# espslider.net
KiCad netlist of a schematic drawn in EAGLE
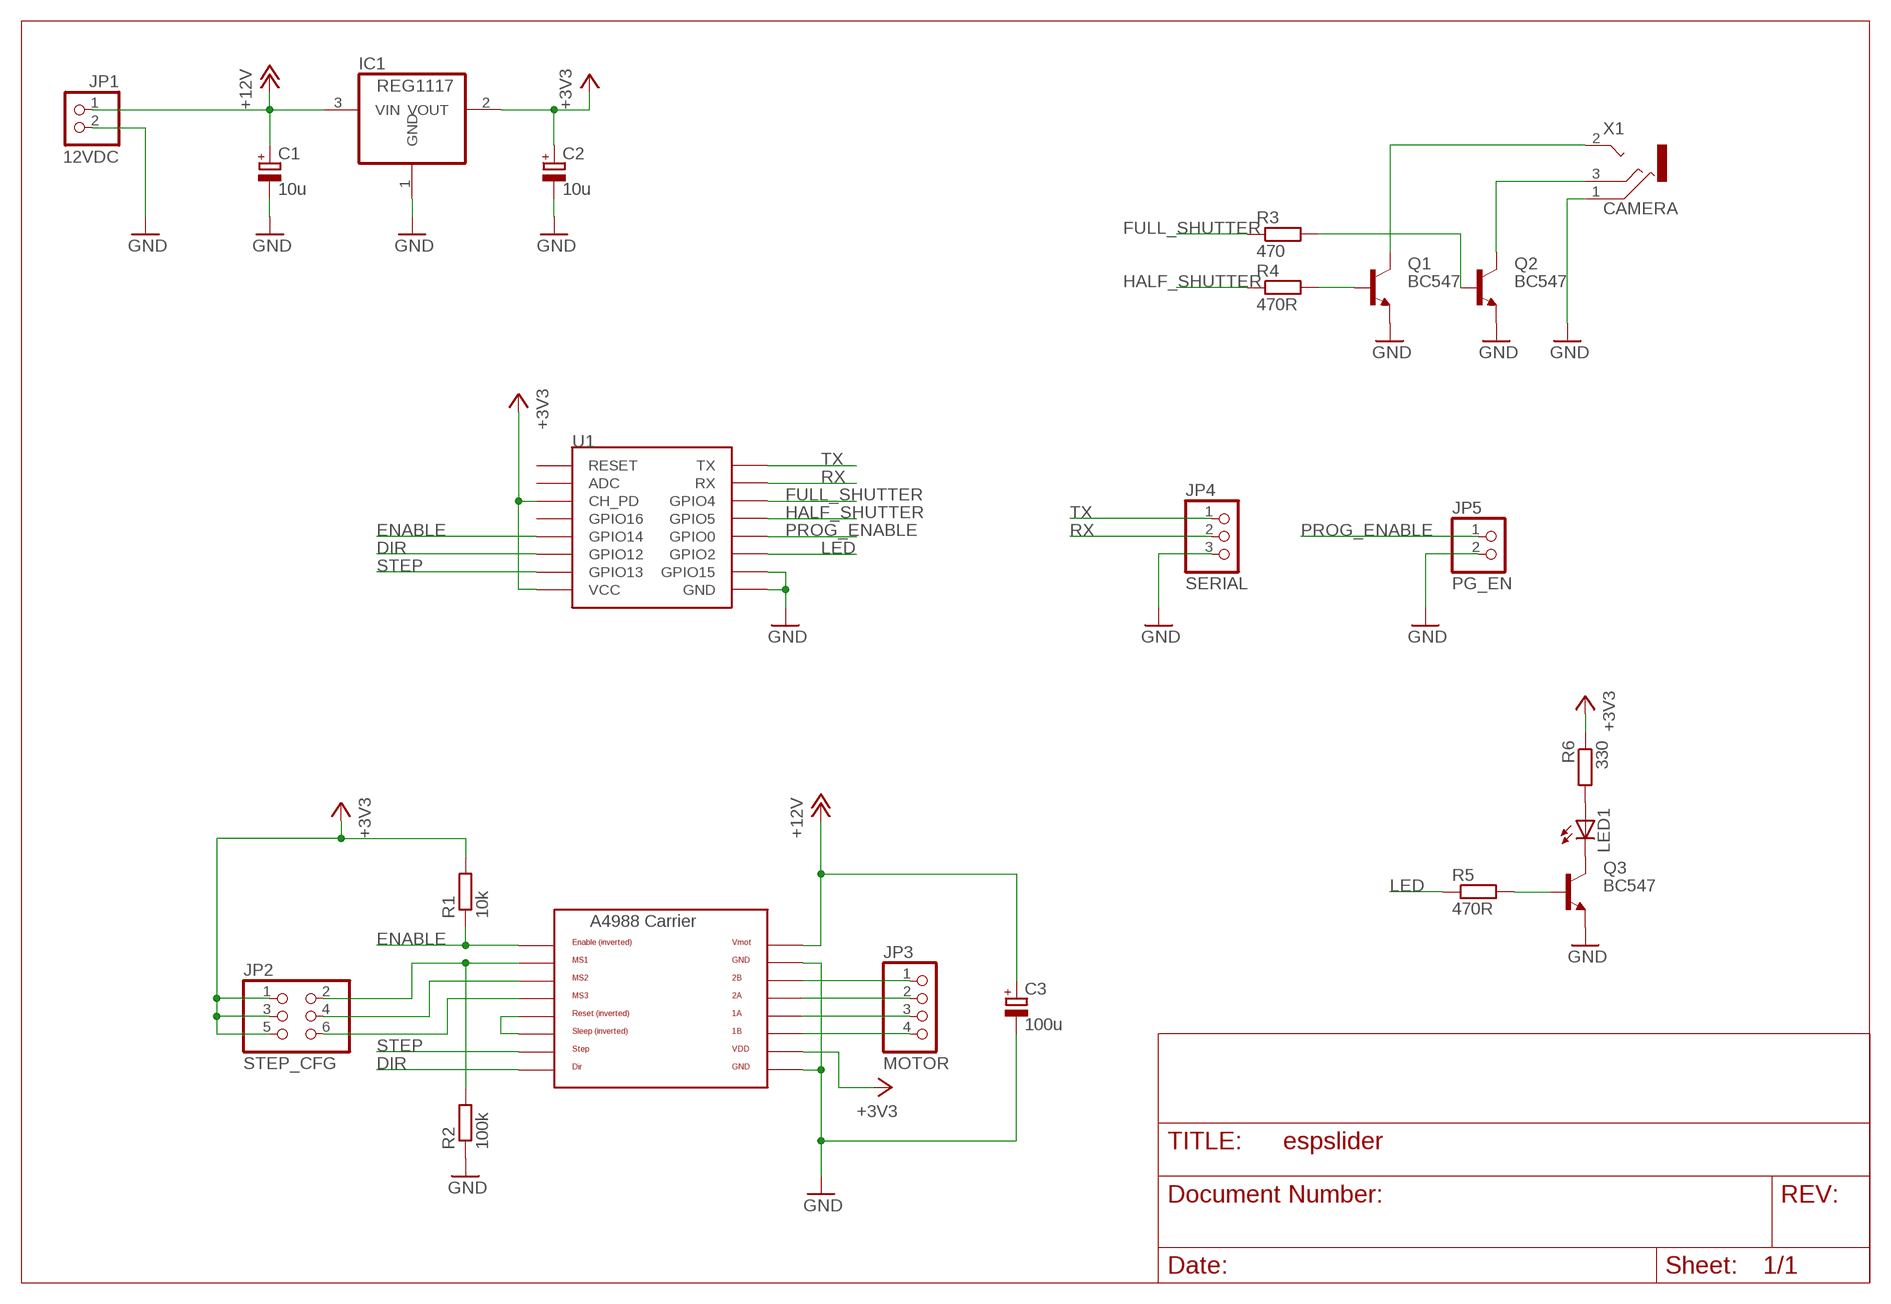
[diagram p0: schematic, sheet 1]

(export (version "E")
  (design (tool "Eeschema 10.0.6"))
  (components
    (comp (ref "C1")
      (value "10u")
      (footprint "eagle-import:E5-5")
      (fields (field (name "MF") "KEMET") (field (name "MPN") "T491C107K010AT"))
      (libsource (lib "eagle-import") (part "CPOL-EUE5-5"))
    )
    (comp (ref "C2")
      (value "10u")
      (footprint "eagle-import:E5-5")
      (fields (field (name "MF") "KEMET") (field (name "MPN") "T491C107K010AT"))
      (libsource (lib "eagle-import") (part "CPOL-EUE5-5"))
    )
    (comp (ref "C3")
      (value "100u")
      (footprint "eagle-import:E5-5")
      (libsource (lib "eagle-import") (part "CPOL-EUE5-5"))
    )
    (comp (ref "IC1")
      (value "REG1117")
      (footprint "eagle-import:SOT223")
      (libsource (lib "eagle-import") (part "REG1117"))
    )
    (comp (ref "JP1")
      (value "12VDC")
      (footprint "eagle-import:1X02")
      (libsource (lib "eagle-import") (part "PINHD-1X2"))
    )
    (comp (ref "JP2")
      (value "STEP_CFG")
      (footprint "eagle-import:2X03")
      (libsource (lib "eagle-import") (part "PINHD-2X3"))
    )
    (comp (ref "JP3")
      (value "MOTOR")
      (footprint "eagle-import:1X04")
      (libsource (lib "eagle-import") (part "PINHD-1X4"))
    )
    (comp (ref "JP4")
      (value "SERIAL")
      (footprint "eagle-import:1X03")
      (libsource (lib "eagle-import") (part "PINHD-1X3"))
    )
    (comp (ref "JP5")
      (value "PG_EN")
      (footprint "eagle-import:1X02")
      (libsource (lib "eagle-import") (part "PINHD-1X2"))
    )
    (comp (ref "LED1")
      (value "LED3MM")
      (footprint "eagle-import:LED3MM")
      (libsource (lib "eagle-import") (part "LED3MM"))
    )
    (comp (ref "Q1")
      (value "BC547")
      (footprint "eagle-import:TO92")
      (libsource (lib "eagle-import") (part "BC547"))
    )
    (comp (ref "Q2")
      (value "BC547")
      (footprint "eagle-import:TO92")
      (libsource (lib "eagle-import") (part "BC547"))
    )
    (comp (ref "Q3")
      (value "BC547")
      (footprint "eagle-import:TO92")
      (libsource (lib "eagle-import") (part "BC547"))
    )
    (comp (ref "R1")
      (value "10k")
      (footprint "eagle-import:0207_7")
      (libsource (lib "eagle-import") (part "R-EU_0207/7"))
    )
    (comp (ref "R2")
      (value "100k")
      (footprint "eagle-import:0207_15")
      (libsource (lib "eagle-import") (part "R-EU_0207/15"))
    )
    (comp (ref "R3")
      (value "470")
      (footprint "eagle-import:0207_7")
      (libsource (lib "eagle-import") (part "R-EU_0207/7"))
    )
    (comp (ref "R4")
      (value "470R")
      (footprint "eagle-import:0207_7")
      (libsource (lib "eagle-import") (part "R-EU_0207/7"))
    )
    (comp (ref "R5")
      (value "470R")
      (footprint "eagle-import:0207_7")
      (libsource (lib "eagle-import") (part "R-EU_0207/7"))
    )
    (comp (ref "R6")
      (value "330")
      (footprint "eagle-import:0207_7")
      (libsource (lib "eagle-import") (part "R-EU_0207/7"))
    )
    (comp (ref "U1")
      (value "ESP12SMD")
      (footprint "eagle-import:ESP12-SMD")
      (libsource (lib "eagle-import") (part "ESP12SMD"))
    )
    (comp (ref "U2")
      (value "A4988BREAKOUT")
      (footprint "eagle-import:A4988BREAKOUT")
      (libsource (lib "eagle-import") (part "A4988BREAKOUT"))
    )
    (comp (ref "X1")
      (value "CAMERA")
      (footprint "eagle-import:1501_05")
      (libsource (lib "eagle-import") (part "1501_04"))
    )
  )
  (nets
    (net (code "1") (name "+3V3") (class "Default")
      (node (ref "C2") (pin "+") (pinfunction "+_+") (pintype "passive"))
      (node (ref "IC1") (pin "2") (pinfunction "VOUT_2") (pintype "output"))
      (node (ref "JP2") (pin "1") (pinfunction "1_1") (pintype "passive"))
      (node (ref "JP2") (pin "3") (pinfunction "3_3") (pintype "passive"))
      (node (ref "JP2") (pin "5") (pinfunction "5_5") (pintype "passive"))
      (node (ref "R1") (pin "2") (pinfunction "2_2") (pintype "passive"))
      (node (ref "R6") (pin "1") (pinfunction "1_1") (pintype "passive"))
      (node (ref "U1") (pin "CH_PD") (pinfunction "CH_PD_CH_PD") (pintype "bidirectional"))
      (node (ref "U1") (pin "VCC") (pinfunction "VCC_VCC") (pintype "bidirectional"))
      (node (ref "U2") (pin "VDD") (pinfunction "VDD_VDD") (pintype "power_in"))
    )
    (net (code "2") (name "+12V") (class "Default")
      (node (ref "C1") (pin "+") (pinfunction "+_+") (pintype "passive"))
      (node (ref "C3") (pin "+") (pinfunction "+_+") (pintype "passive"))
      (node (ref "IC1") (pin "3") (pinfunction "VIN_3") (pintype "input"))
      (node (ref "JP1") (pin "1") (pinfunction "1_1") (pintype "passive"))
      (node (ref "U2") (pin "VMOT") (pinfunction "VMOT_VMOT") (pintype "power_in"))
    )
    (net (code "3") (name "/DIR") (class "Default")
      (node (ref "U1") (pin "GPIO12") (pinfunction "GPIO12_GPIO12") (pintype "bidirectional"))
      (node (ref "U2") (pin "DIR") (pinfunction "DIR_DIR") (pintype "input"))
    )
    (net (code "4") (name "/ENABLE") (class "Default")
      (node (ref "R1") (pin "1") (pinfunction "1_1") (pintype "passive"))
      (node (ref "U1") (pin "GPIO14") (pinfunction "GPIO14_GPIO14") (pintype "bidirectional"))
      (node (ref "U2") (pin "EN") (pinfunction "EN_EN") (pintype "input"))
    )
    (net (code "5") (name "/FULL_SHUTTER") (class "Default")
      (node (ref "R3") (pin "1") (pinfunction "1_1") (pintype "passive"))
      (node (ref "U1") (pin "GPIO4") (pinfunction "GPIO4_GPIO4") (pintype "bidirectional"))
    )
    (net (code "6") (name "/HALF_SHUTTER") (class "Default")
      (node (ref "R4") (pin "1") (pinfunction "1_1") (pintype "passive"))
      (node (ref "U1") (pin "GPIO5") (pinfunction "GPIO5_GPIO5") (pintype "bidirectional"))
    )
    (net (code "7") (name "/LED") (class "Default")
      (node (ref "R5") (pin "1") (pinfunction "1_1") (pintype "passive"))
      (node (ref "U1") (pin "GPIO2") (pinfunction "GPIO2_GPIO2") (pintype "bidirectional"))
    )
    (net (code "8") (name "/PROG_ENABLE") (class "Default")
      (node (ref "JP5") (pin "1") (pinfunction "1_1") (pintype "passive"))
      (node (ref "U1") (pin "GPIO0") (pinfunction "GPIO0_GPIO0") (pintype "bidirectional"))
    )
    (net (code "9") (name "/RX") (class "Default")
      (node (ref "JP4") (pin "2") (pinfunction "2_2") (pintype "passive"))
      (node (ref "U1") (pin "RXD0") (pinfunction "RX_RXD0") (pintype "bidirectional"))
    )
    (net (code "10") (name "/STEP") (class "Default")
      (node (ref "U1") (pin "GPIO13") (pinfunction "GPIO13_GPIO13") (pintype "bidirectional"))
      (node (ref "U2") (pin "STEP") (pinfunction "STEP_STEP") (pintype "input"))
    )
    (net (code "11") (name "/TX") (class "Default")
      (node (ref "JP4") (pin "1") (pinfunction "1_1") (pintype "passive"))
      (node (ref "U1") (pin "TXD0") (pinfunction "TX_TXD0") (pintype "bidirectional"))
    )
    (net (code "12") (name "GND") (class "Default")
      (node (ref "C1") (pin "-") (pinfunction "-_-") (pintype "passive"))
      (node (ref "C2") (pin "-") (pinfunction "-_-") (pintype "passive"))
      (node (ref "C3") (pin "-") (pinfunction "-_-") (pintype "passive"))
      (node (ref "IC1") (pin "1") (pinfunction "GND_1") (pintype "power_in"))
      (node (ref "JP1") (pin "2") (pinfunction "2_2") (pintype "passive"))
      (node (ref "JP4") (pin "3") (pinfunction "3_3") (pintype "passive"))
      (node (ref "JP5") (pin "2") (pinfunction "2_2") (pintype "passive"))
      (node (ref "Q1") (pin "1") (pinfunction "E_1") (pintype "passive"))
      (node (ref "Q2") (pin "1") (pinfunction "E_1") (pintype "passive"))
      (node (ref "Q3") (pin "1") (pinfunction "E_1") (pintype "passive"))
      (node (ref "R2") (pin "1") (pinfunction "1_1") (pintype "passive"))
      (node (ref "U1") (pin "GND") (pinfunction "GND_GND") (pintype "bidirectional"))
      (node (ref "U1") (pin "GPIO15") (pinfunction "GPIO15_GPIO15") (pintype "bidirectional"))
      (node (ref "U2") (pin "GND") (pinfunction "GND_GND") (pintype "power_in"))
      (node (ref "U2") (pin "GND@0") (pinfunction "GND_GND@0") (pintype "power_in"))
      (node (ref "X1") (pin "1") (pinfunction "1_1") (pintype "passive"))
    )
    (net (code "13") (name "Net-(JP2-Pad2)") (class "Default")
      (node (ref "JP2") (pin "2") (pinfunction "2_2") (pintype "passive"))
      (node (ref "R2") (pin "2") (pinfunction "2_2") (pintype "passive"))
      (node (ref "U2") (pin "MS1") (pinfunction "MS1_MS1") (pintype "input"))
    )
    (net (code "14") (name "Net-(JP2-Pad4)") (class "Default")
      (node (ref "JP2") (pin "4") (pinfunction "4_4") (pintype "passive"))
      (node (ref "U2") (pin "MS2") (pinfunction "MS2_MS2") (pintype "input"))
    )
    (net (code "15") (name "Net-(JP2-Pad6)") (class "Default")
      (node (ref "JP2") (pin "6") (pinfunction "6_6") (pintype "passive"))
      (node (ref "U2") (pin "MS3") (pinfunction "MS3_MS3") (pintype "input"))
    )
    (net (code "16") (name "Net-(JP3-Pad1)") (class "Default")
      (node (ref "JP3") (pin "1") (pinfunction "1_1") (pintype "passive"))
      (node (ref "U2") (pin "2B") (pinfunction "2B_2B") (pintype "output"))
    )
    (net (code "17") (name "Net-(JP3-Pad2)") (class "Default")
      (node (ref "JP3") (pin "2") (pinfunction "2_2") (pintype "passive"))
      (node (ref "U2") (pin "2A") (pinfunction "2A_2A") (pintype "output"))
    )
    (net (code "18") (name "Net-(JP3-Pad3)") (class "Default")
      (node (ref "JP3") (pin "3") (pinfunction "3_3") (pintype "passive"))
      (node (ref "U2") (pin "1A") (pinfunction "1A_1A") (pintype "output"))
    )
    (net (code "19") (name "Net-(JP3-Pad4)") (class "Default")
      (node (ref "JP3") (pin "4") (pinfunction "4_4") (pintype "passive"))
      (node (ref "U2") (pin "1B") (pinfunction "1B_1B") (pintype "output"))
    )
    (net (code "20") (name "Net-(LED1-C)") (class "Default")
      (node (ref "LED1") (pin "K") (pinfunction "C_K") (pintype "passive"))
      (node (ref "Q3") (pin "3") (pinfunction "C_3") (pintype "passive"))
    )
    (net (code "21") (name "Net-(LED1-PadA)") (class "Default")
      (node (ref "LED1") (pin "A") (pinfunction "A_A") (pintype "passive"))
      (node (ref "R6") (pin "2") (pinfunction "2_2") (pintype "passive"))
    )
    (net (code "22") (name "Net-(Q1-B)") (class "Default")
      (node (ref "Q1") (pin "2") (pinfunction "B_2") (pintype "passive"))
      (node (ref "R4") (pin "2") (pinfunction "2_2") (pintype "passive"))
    )
    (net (code "23") (name "Net-(Q1-C)") (class "Default")
      (node (ref "Q1") (pin "3") (pinfunction "C_3") (pintype "passive"))
      (node (ref "X1") (pin "2") (pinfunction "2_2") (pintype "passive"))
    )
    (net (code "24") (name "Net-(Q2-B)") (class "Default")
      (node (ref "Q2") (pin "2") (pinfunction "B_2") (pintype "passive"))
      (node (ref "R3") (pin "2") (pinfunction "2_2") (pintype "passive"))
    )
    (net (code "25") (name "Net-(Q2-C)") (class "Default")
      (node (ref "Q2") (pin "3") (pinfunction "C_3") (pintype "passive"))
      (node (ref "X1") (pin "3") (pinfunction "3_3") (pintype "passive"))
    )
    (net (code "26") (name "Net-(Q3-B)") (class "Default")
      (node (ref "Q3") (pin "2") (pinfunction "B_2") (pintype "passive"))
      (node (ref "R5") (pin "2") (pinfunction "2_2") (pintype "passive"))
    )
    (net (code "27") (name "Net-(U2-SLEEP)") (class "Default")
      (node (ref "U2") (pin "RST") (pinfunction "RST_RST") (pintype "input"))
      (node (ref "U2") (pin "SLP") (pinfunction "SLEEP_SLP") (pintype "input"))
    )
    (net (code "28") (name "unconnected-(U1-PadADC)") (class "Default")
      (node (ref "U1") (pin "ADC") (pinfunction "ADC_ADC") (pintype "bidirectional"))
    )
    (net (code "29") (name "unconnected-(U1-PadGPIO16)") (class "Default")
      (node (ref "U1") (pin "GPIO16") (pinfunction "GPIO16_GPIO16") (pintype "bidirectional"))
    )
    (net (code "30") (name "unconnected-(U1-PadRESET)") (class "Default")
      (node (ref "U1") (pin "RESET") (pinfunction "RESET_RESET") (pintype "bidirectional"))
    )
  )
)
